# Mono_Crossover_R1.net
KiCad netlist of a schematic drawn in EAGLE
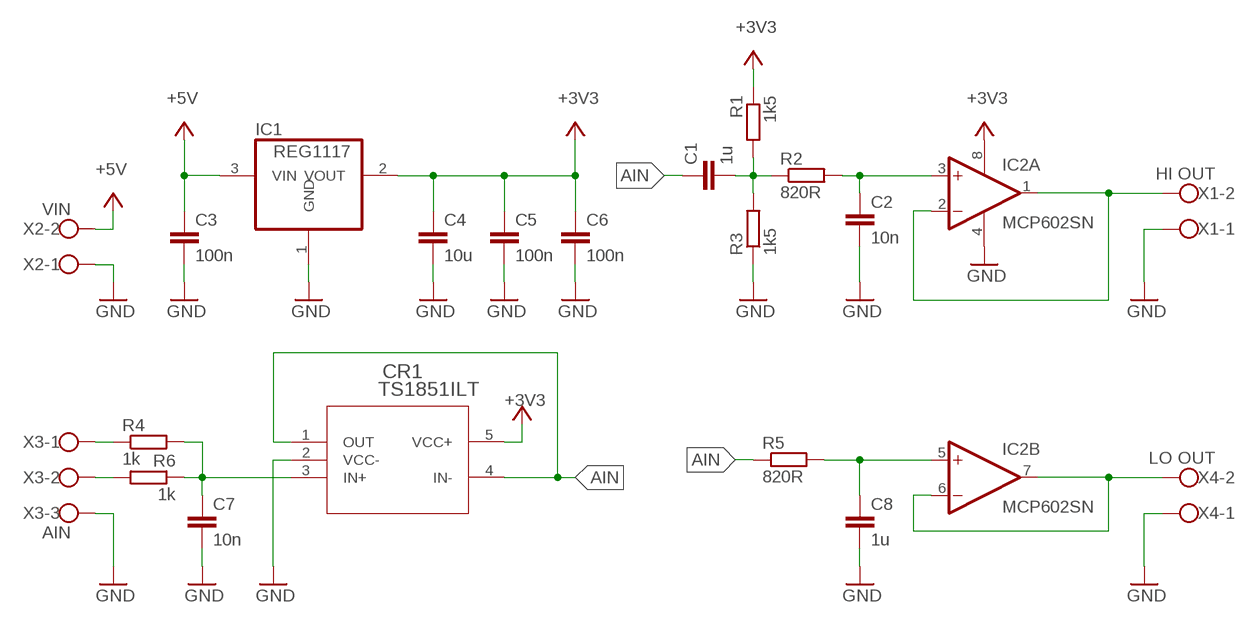
[diagram p0: schematic, sheet 1]

(export (version "E")
  (design (tool "Eeschema 10.0.6"))
  (components
    (comp (ref "C1")
      (value "1u")
      (footprint "eagle-import:C0805")
      (libsource (lib "eagle-import") (part "C-EUC0805"))
    )
    (comp (ref "C2")
      (value "10n")
      (footprint "eagle-import:C0603")
      (libsource (lib "eagle-import") (part "C-EUC0603"))
    )
    (comp (ref "C3")
      (value "100n")
      (footprint "eagle-import:C0603")
      (libsource (lib "eagle-import") (part "C-EUC0603"))
    )
    (comp (ref "C4")
      (value "10u")
      (footprint "eagle-import:C1206")
      (libsource (lib "eagle-import") (part "C-EUC1206"))
    )
    (comp (ref "C5")
      (value "100n")
      (footprint "eagle-import:C0603")
      (libsource (lib "eagle-import") (part "C-EUC0603"))
    )
    (comp (ref "C6")
      (value "100n")
      (footprint "eagle-import:C0603")
      (libsource (lib "eagle-import") (part "C-EUC0603"))
    )
    (comp (ref "C7")
      (value "10n")
      (footprint "eagle-import:C0603")
      (libsource (lib "eagle-import") (part "C-EUC0603"))
    )
    (comp (ref "C8")
      (value "1u")
      (footprint "eagle-import:C0805")
      (libsource (lib "eagle-import") (part "C-EUC0805"))
    )
    (comp (ref "CR1")
      (value "TS1851ILT")
      (footprint "eagle-import:SOT23-5L_STM")
      (fields (field (name "COPYRIGHT") "Copyright (C) 2022 Ultra Librarian. All rights reserved."))
      (libsource (lib "eagle-import") (part "TS1851ILT"))
    )
    (comp (ref "IC1")
      (value "REG1117")
      (footprint "eagle-import:SOT223")
      (libsource (lib "eagle-import") (part "REG1117"))
    )
    (comp (ref "IC2")
      (value "MCP602SN")
      (footprint "eagle-import:SO08")
      (libsource (lib "eagle-import") (part "MCP602SN"))
    )
    (comp (ref "R1")
      (value "1k5")
      (footprint "eagle-import:R0805")
      (libsource (lib "eagle-import") (part "R-EU_R0805"))
    )
    (comp (ref "R2")
      (value "820R")
      (footprint "eagle-import:R1206")
      (libsource (lib "eagle-import") (part "R-EU_R1206"))
    )
    (comp (ref "R3")
      (value "1k5")
      (footprint "eagle-import:R0805")
      (libsource (lib "eagle-import") (part "R-EU_R0805"))
    )
    (comp (ref "R4")
      (value "1k")
      (footprint "eagle-import:R0603")
      (libsource (lib "eagle-import") (part "R-EU_R0603"))
    )
    (comp (ref "R5")
      (value "820R")
      (footprint "eagle-import:R1206")
      (libsource (lib "eagle-import") (part "R-EU_R1206"))
    )
    (comp (ref "R6")
      (value "1k")
      (footprint "eagle-import:R0603")
      (libsource (lib "eagle-import") (part "R-EU_R0603"))
    )
    (comp (ref "X1")
      (value "HI OUT")
      (footprint "eagle-import:W237-102")
      (fields (field (name "MPN") "237-102"))
      (libsource (lib "eagle-import") (part "W237-102"))
    )
    (comp (ref "X2")
      (value "VIN")
      (footprint "eagle-import:W237-102")
      (fields (field (name "MPN") "237-102"))
      (libsource (lib "eagle-import") (part "W237-102"))
    )
    (comp (ref "X3")
      (value "AIN")
      (footprint "eagle-import:W237-103")
      (fields (field (name "MPN") "237-103"))
      (libsource (lib "eagle-import") (part "W237-103"))
    )
    (comp (ref "X4")
      (value "LO OUT")
      (footprint "eagle-import:W237-102")
      (fields (field (name "MPN") "237-102"))
      (libsource (lib "eagle-import") (part "W237-102"))
    )
  )
  (nets
    (net (code "1") (name "+3V3") (class "Default")
      (node (ref "C4") (pin "1") (pinfunction "1_1") (pintype "passive"))
      (node (ref "C5") (pin "1") (pinfunction "1_1") (pintype "passive"))
      (node (ref "C6") (pin "1") (pinfunction "1_1") (pintype "passive"))
      (node (ref "CR1") (pin "5") (pinfunction "VCC+_5") (pintype "power_in"))
      (node (ref "IC1") (pin "2") (pinfunction "VOUT_2") (pintype "output"))
      (node (ref "IC2") (pin "8") (pinfunction "V+_8") (pintype "power_in"))
      (node (ref "R1") (pin "1") (pinfunction "1_1") (pintype "passive"))
    )
    (net (code "2") (name "+5V") (class "Default")
      (node (ref "C3") (pin "1") (pinfunction "1_1") (pintype "passive"))
      (node (ref "IC1") (pin "3") (pinfunction "VIN_3") (pintype "input"))
      (node (ref "X2") (pin "2") (pinfunction "KL_2") (pintype "passive"))
    )
    (net (code "3") (name "AIN") (class "Default")
      (node (ref "C1") (pin "1") (pinfunction "1_1") (pintype "passive"))
      (node (ref "CR1") (pin "1") (pinfunction "OUT_1") (pintype "output"))
      (node (ref "CR1") (pin "4") (pinfunction "IN-_4") (pintype "input"))
      (node (ref "R5") (pin "1") (pinfunction "1_1") (pintype "passive"))
    )
    (net (code "4") (name "GND") (class "Default")
      (node (ref "C2") (pin "2") (pinfunction "2_2") (pintype "passive"))
      (node (ref "C3") (pin "2") (pinfunction "2_2") (pintype "passive"))
      (node (ref "C4") (pin "2") (pinfunction "2_2") (pintype "passive"))
      (node (ref "C5") (pin "2") (pinfunction "2_2") (pintype "passive"))
      (node (ref "C6") (pin "2") (pinfunction "2_2") (pintype "passive"))
      (node (ref "C7") (pin "2") (pinfunction "2_2") (pintype "passive"))
      (node (ref "C8") (pin "2") (pinfunction "2_2") (pintype "passive"))
      (node (ref "CR1") (pin "2") (pinfunction "VCC-_2") (pintype "power_in"))
      (node (ref "IC1") (pin "1") (pinfunction "GND_1") (pintype "power_in"))
      (node (ref "IC2") (pin "4") (pinfunction "V-_4") (pintype "power_in"))
      (node (ref "R3") (pin "1") (pinfunction "1_1") (pintype "passive"))
      (node (ref "X1") (pin "1") (pinfunction "KL_1") (pintype "passive"))
      (node (ref "X2") (pin "1") (pinfunction "KL_1") (pintype "passive"))
      (node (ref "X3") (pin "3") (pinfunction "KL_3") (pintype "passive"))
      (node (ref "X4") (pin "1") (pinfunction "KL_1") (pintype "passive"))
    )
    (net (code "5") (name "Net-(C1-Pad2)") (class "Default")
      (node (ref "C1") (pin "2") (pinfunction "2_2") (pintype "passive"))
      (node (ref "R1") (pin "2") (pinfunction "2_2") (pintype "passive"))
      (node (ref "R2") (pin "1") (pinfunction "1_1") (pintype "passive"))
      (node (ref "R3") (pin "2") (pinfunction "2_2") (pintype "passive"))
    )
    (net (code "6") (name "Net-(CR1-IN+)") (class "Default")
      (node (ref "C7") (pin "1") (pinfunction "1_1") (pintype "passive"))
      (node (ref "CR1") (pin "3") (pinfunction "IN+_3") (pintype "input"))
      (node (ref "R4") (pin "2") (pinfunction "2_2") (pintype "passive"))
      (node (ref "R6") (pin "1") (pinfunction "1_1") (pintype "passive"))
    )
    (net (code "7") (name "Net-(IC2A-+IN)") (class "Default")
      (node (ref "C2") (pin "1") (pinfunction "1_1") (pintype "passive"))
      (node (ref "IC2") (pin "3") (pinfunction "+IN_3") (pintype "input"))
      (node (ref "R2") (pin "2") (pinfunction "2_2") (pintype "passive"))
    )
    (net (code "8") (name "Net-(IC2A--IN)") (class "Default")
      (node (ref "IC2") (pin "1") (pinfunction "OUT_1") (pintype "output"))
      (node (ref "IC2") (pin "2") (pinfunction "-IN_2") (pintype "input"))
      (node (ref "X1") (pin "2") (pinfunction "KL_2") (pintype "passive"))
    )
    (net (code "9") (name "Net-(IC2B-+IN)") (class "Default")
      (node (ref "C8") (pin "1") (pinfunction "1_1") (pintype "passive"))
      (node (ref "IC2") (pin "5") (pinfunction "+IN_5") (pintype "input"))
      (node (ref "R5") (pin "2") (pinfunction "2_2") (pintype "passive"))
    )
    (net (code "10") (name "Net-(IC2B--IN)") (class "Default")
      (node (ref "IC2") (pin "6") (pinfunction "-IN_6") (pintype "input"))
      (node (ref "IC2") (pin "7") (pinfunction "OUT_7") (pintype "output"))
      (node (ref "X4") (pin "2") (pinfunction "KL_2") (pintype "passive"))
    )
    (net (code "11") (name "Net-(X3A-KL)") (class "Default")
      (node (ref "R4") (pin "1") (pinfunction "1_1") (pintype "passive"))
      (node (ref "X3") (pin "1") (pinfunction "KL_1") (pintype "passive"))
    )
    (net (code "12") (name "Net-(X3B-KL)") (class "Default")
      (node (ref "R6") (pin "2") (pinfunction "2_2") (pintype "passive"))
      (node (ref "X3") (pin "2") (pinfunction "KL_2") (pintype "passive"))
    )
  )
)
